# deska.net
KiCad netlist of a schematic drawn in EAGLE
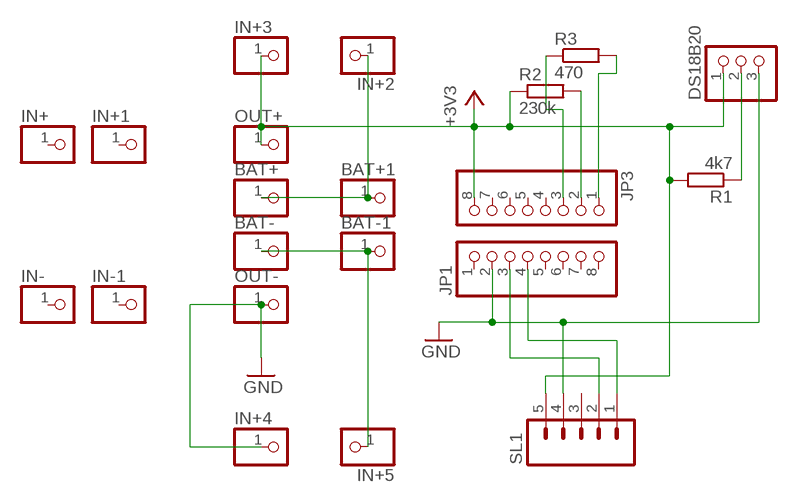
[diagram p0: schematic, sheet 1]

(export (version "E")
  (design (tool "Eeschema 10.0.6"))
  (components
    (comp (ref "BAT+")
      (value "PINHD-1X1")
      (footprint "eagle-import:1X01")
      (libsource (lib "eagle-import") (part "PINHD-1X1"))
    )
    (comp (ref "BAT+1")
      (value "PINHD-1X1")
      (footprint "eagle-import:1X01")
      (libsource (lib "eagle-import") (part "PINHD-1X1"))
    )
    (comp (ref "BAT-")
      (value "PINHD-1X1")
      (footprint "eagle-import:1X01")
      (libsource (lib "eagle-import") (part "PINHD-1X1"))
    )
    (comp (ref "BAT-1")
      (value "PINHD-1X1")
      (footprint "eagle-import:1X01")
      (libsource (lib "eagle-import") (part "PINHD-1X1"))
    )
    (comp (ref "DS18B20")
      (value "PINHD-1X3")
      (footprint "eagle-import:1X03")
      (libsource (lib "eagle-import") (part "PINHD-1X3"))
    )
    (comp (ref "IN+")
      (value "PINHD-1X1")
      (footprint "eagle-import:1X01")
      (libsource (lib "eagle-import") (part "PINHD-1X1"))
    )
    (comp (ref "IN+1")
      (value "PINHD-1X1")
      (footprint "eagle-import:1X01")
      (libsource (lib "eagle-import") (part "PINHD-1X1"))
    )
    (comp (ref "IN+2")
      (value "PINHD-1X1")
      (footprint "eagle-import:1X01")
      (libsource (lib "eagle-import") (part "PINHD-1X1"))
    )
    (comp (ref "IN+3")
      (value "PINHD-1X1")
      (footprint "eagle-import:1X01")
      (libsource (lib "eagle-import") (part "PINHD-1X1"))
    )
    (comp (ref "IN+4")
      (value "PINHD-1X1")
      (footprint "eagle-import:1X01")
      (libsource (lib "eagle-import") (part "PINHD-1X1"))
    )
    (comp (ref "IN+5")
      (value "PINHD-1X1")
      (footprint "eagle-import:1X01")
      (libsource (lib "eagle-import") (part "PINHD-1X1"))
    )
    (comp (ref "IN-")
      (value "PINHD-1X1")
      (footprint "eagle-import:1X01")
      (libsource (lib "eagle-import") (part "PINHD-1X1"))
    )
    (comp (ref "IN-1")
      (value "PINHD-1X1")
      (footprint "eagle-import:1X01")
      (libsource (lib "eagle-import") (part "PINHD-1X1"))
    )
    (comp (ref "JP1")
      (value "PINHD-1X8")
      (footprint "eagle-import:1X08")
      (libsource (lib "eagle-import") (part "PINHD-1X8"))
    )
    (comp (ref "JP3")
      (value "PINHD-1X8")
      (footprint "eagle-import:1X08")
      (libsource (lib "eagle-import") (part "PINHD-1X8"))
    )
    (comp (ref "OUT+")
      (value "PINHD-1X1")
      (footprint "eagle-import:1X01")
      (libsource (lib "eagle-import") (part "PINHD-1X1"))
    )
    (comp (ref "OUT-")
      (value "PINHD-1X1")
      (footprint "eagle-import:1X01")
      (libsource (lib "eagle-import") (part "PINHD-1X1"))
    )
    (comp (ref "R1")
      (value "4k7")
      (footprint "eagle-import:0204_7")
      (libsource (lib "eagle-import") (part "R-EU_0204/7"))
    )
    (comp (ref "R2")
      (value "230k")
      (footprint "eagle-import:0204_7")
      (libsource (lib "eagle-import") (part "R-EU_0204/7"))
    )
    (comp (ref "R3")
      (value "470")
      (footprint "eagle-import:0204_7")
      (libsource (lib "eagle-import") (part "R-EU_0204/7"))
    )
    (comp (ref "SL1")
      (value "M05")
      (footprint "eagle-import:05P")
      (libsource (lib "eagle-import") (part "M05"))
    )
  )
  (nets
    (net (code "1") (name "+3V3") (class "Default")
      (node (ref "DS18B20") (pin "1") (pinfunction "1_1") (pintype "passive"))
      (node (ref "IN+3") (pin "1") (pinfunction "1_1") (pintype "passive"))
      (node (ref "JP3") (pin "8") (pinfunction "8_8") (pintype "passive"))
      (node (ref "OUT+") (pin "1") (pinfunction "1_1") (pintype "passive"))
      (node (ref "R1") (pin "2") (pinfunction "2_2") (pintype "passive"))
      (node (ref "R2") (pin "1") (pinfunction "1_1") (pintype "passive"))
      (node (ref "SL1") (pin "5") (pinfunction "5_5") (pintype "passive"))
    )
    (net (code "2") (name "GND") (class "Default")
      (node (ref "DS18B20") (pin "3") (pinfunction "3_3") (pintype "passive"))
      (node (ref "IN+4") (pin "1") (pinfunction "1_1") (pintype "passive"))
      (node (ref "JP1") (pin "2") (pinfunction "2_2") (pintype "passive"))
      (node (ref "OUT-") (pin "1") (pinfunction "1_1") (pintype "passive"))
      (node (ref "SL1") (pin "4") (pinfunction "4_4") (pintype "passive"))
    )
    (net (code "3") (name "Net-(BAT+-Pad1)") (class "Default")
      (node (ref "BAT+") (pin "1") (pinfunction "1_1") (pintype "passive"))
      (node (ref "BAT+1") (pin "1") (pinfunction "1_1") (pintype "passive"))
      (node (ref "IN+2") (pin "1") (pinfunction "1_1") (pintype "passive"))
    )
    (net (code "4") (name "Net-(BAT--Pad1)") (class "Default")
      (node (ref "BAT-") (pin "1") (pinfunction "1_1") (pintype "passive"))
      (node (ref "BAT-1") (pin "1") (pinfunction "1_1") (pintype "passive"))
      (node (ref "IN+5") (pin "1") (pinfunction "1_1") (pintype "passive"))
    )
    (net (code "5") (name "Net-(DS18B20-Pad2)") (class "Default")
      (node (ref "DS18B20") (pin "2") (pinfunction "2_2") (pintype "passive"))
      (node (ref "R1") (pin "1") (pinfunction "1_1") (pintype "passive"))
    )
    (net (code "6") (name "Net-(JP1-Pad3)") (class "Default")
      (node (ref "JP1") (pin "3") (pinfunction "3_3") (pintype "passive"))
      (node (ref "SL1") (pin "2") (pinfunction "2_2") (pintype "passive"))
    )
    (net (code "7") (name "Net-(JP1-Pad4)") (class "Default")
      (node (ref "JP1") (pin "4") (pinfunction "4_4") (pintype "passive"))
      (node (ref "SL1") (pin "1") (pinfunction "1_1") (pintype "passive"))
    )
    (net (code "8") (name "Net-(JP3-Pad1)") (class "Default")
      (node (ref "JP3") (pin "1") (pinfunction "1_1") (pintype "passive"))
      (node (ref "R3") (pin "2") (pinfunction "2_2") (pintype "passive"))
    )
    (net (code "9") (name "Net-(JP3-Pad2)") (class "Default")
      (node (ref "JP3") (pin "2") (pinfunction "2_2") (pintype "passive"))
      (node (ref "R2") (pin "2") (pinfunction "2_2") (pintype "passive"))
    )
    (net (code "10") (name "Net-(JP3-Pad3)") (class "Default")
      (node (ref "JP3") (pin "3") (pinfunction "3_3") (pintype "passive"))
      (node (ref "R3") (pin "1") (pinfunction "1_1") (pintype "passive"))
    )
    (net (code "11") (name "unconnected-(IN+-Pad1)") (class "Default")
      (node (ref "IN+") (pin "1") (pinfunction "1_1") (pintype "passive"))
    )
    (net (code "12") (name "unconnected-(IN+1-Pad1)") (class "Default")
      (node (ref "IN+1") (pin "1") (pinfunction "1_1") (pintype "passive"))
    )
    (net (code "13") (name "unconnected-(IN--Pad1)") (class "Default")
      (node (ref "IN-") (pin "1") (pinfunction "1_1") (pintype "passive"))
    )
    (net (code "14") (name "unconnected-(IN-1-Pad1)") (class "Default")
      (node (ref "IN-1") (pin "1") (pinfunction "1_1") (pintype "passive"))
    )
    (net (code "15") (name "unconnected-(JP1-Pad1)") (class "Default")
      (node (ref "JP1") (pin "1") (pinfunction "1_1") (pintype "passive"))
    )
    (net (code "16") (name "unconnected-(JP1-Pad5)") (class "Default")
      (node (ref "JP1") (pin "5") (pinfunction "5_5") (pintype "passive"))
    )
    (net (code "17") (name "unconnected-(JP1-Pad6)") (class "Default")
      (node (ref "JP1") (pin "6") (pinfunction "6_6") (pintype "passive"))
    )
    (net (code "18") (name "unconnected-(JP1-Pad7)") (class "Default")
      (node (ref "JP1") (pin "7") (pinfunction "7_7") (pintype "passive"))
    )
    (net (code "19") (name "unconnected-(JP1-Pad8)") (class "Default")
      (node (ref "JP1") (pin "8") (pinfunction "8_8") (pintype "passive"))
    )
    (net (code "20") (name "unconnected-(JP3-Pad4)") (class "Default")
      (node (ref "JP3") (pin "4") (pinfunction "4_4") (pintype "passive"))
    )
    (net (code "21") (name "unconnected-(JP3-Pad5)") (class "Default")
      (node (ref "JP3") (pin "5") (pinfunction "5_5") (pintype "passive"))
    )
    (net (code "22") (name "unconnected-(JP3-Pad6)") (class "Default")
      (node (ref "JP3") (pin "6") (pinfunction "6_6") (pintype "passive"))
    )
    (net (code "23") (name "unconnected-(JP3-Pad7)") (class "Default")
      (node (ref "JP3") (pin "7") (pinfunction "7_7") (pintype "passive"))
    )
    (net (code "24") (name "unconnected-(SL1-Pad3)") (class "Default")
      (node (ref "SL1") (pin "3") (pinfunction "3_3") (pintype "passive"))
    )
  )
)
